# OpenEVSE_PLUS_v3.net
KiCad netlist of a schematic drawn in EAGLE
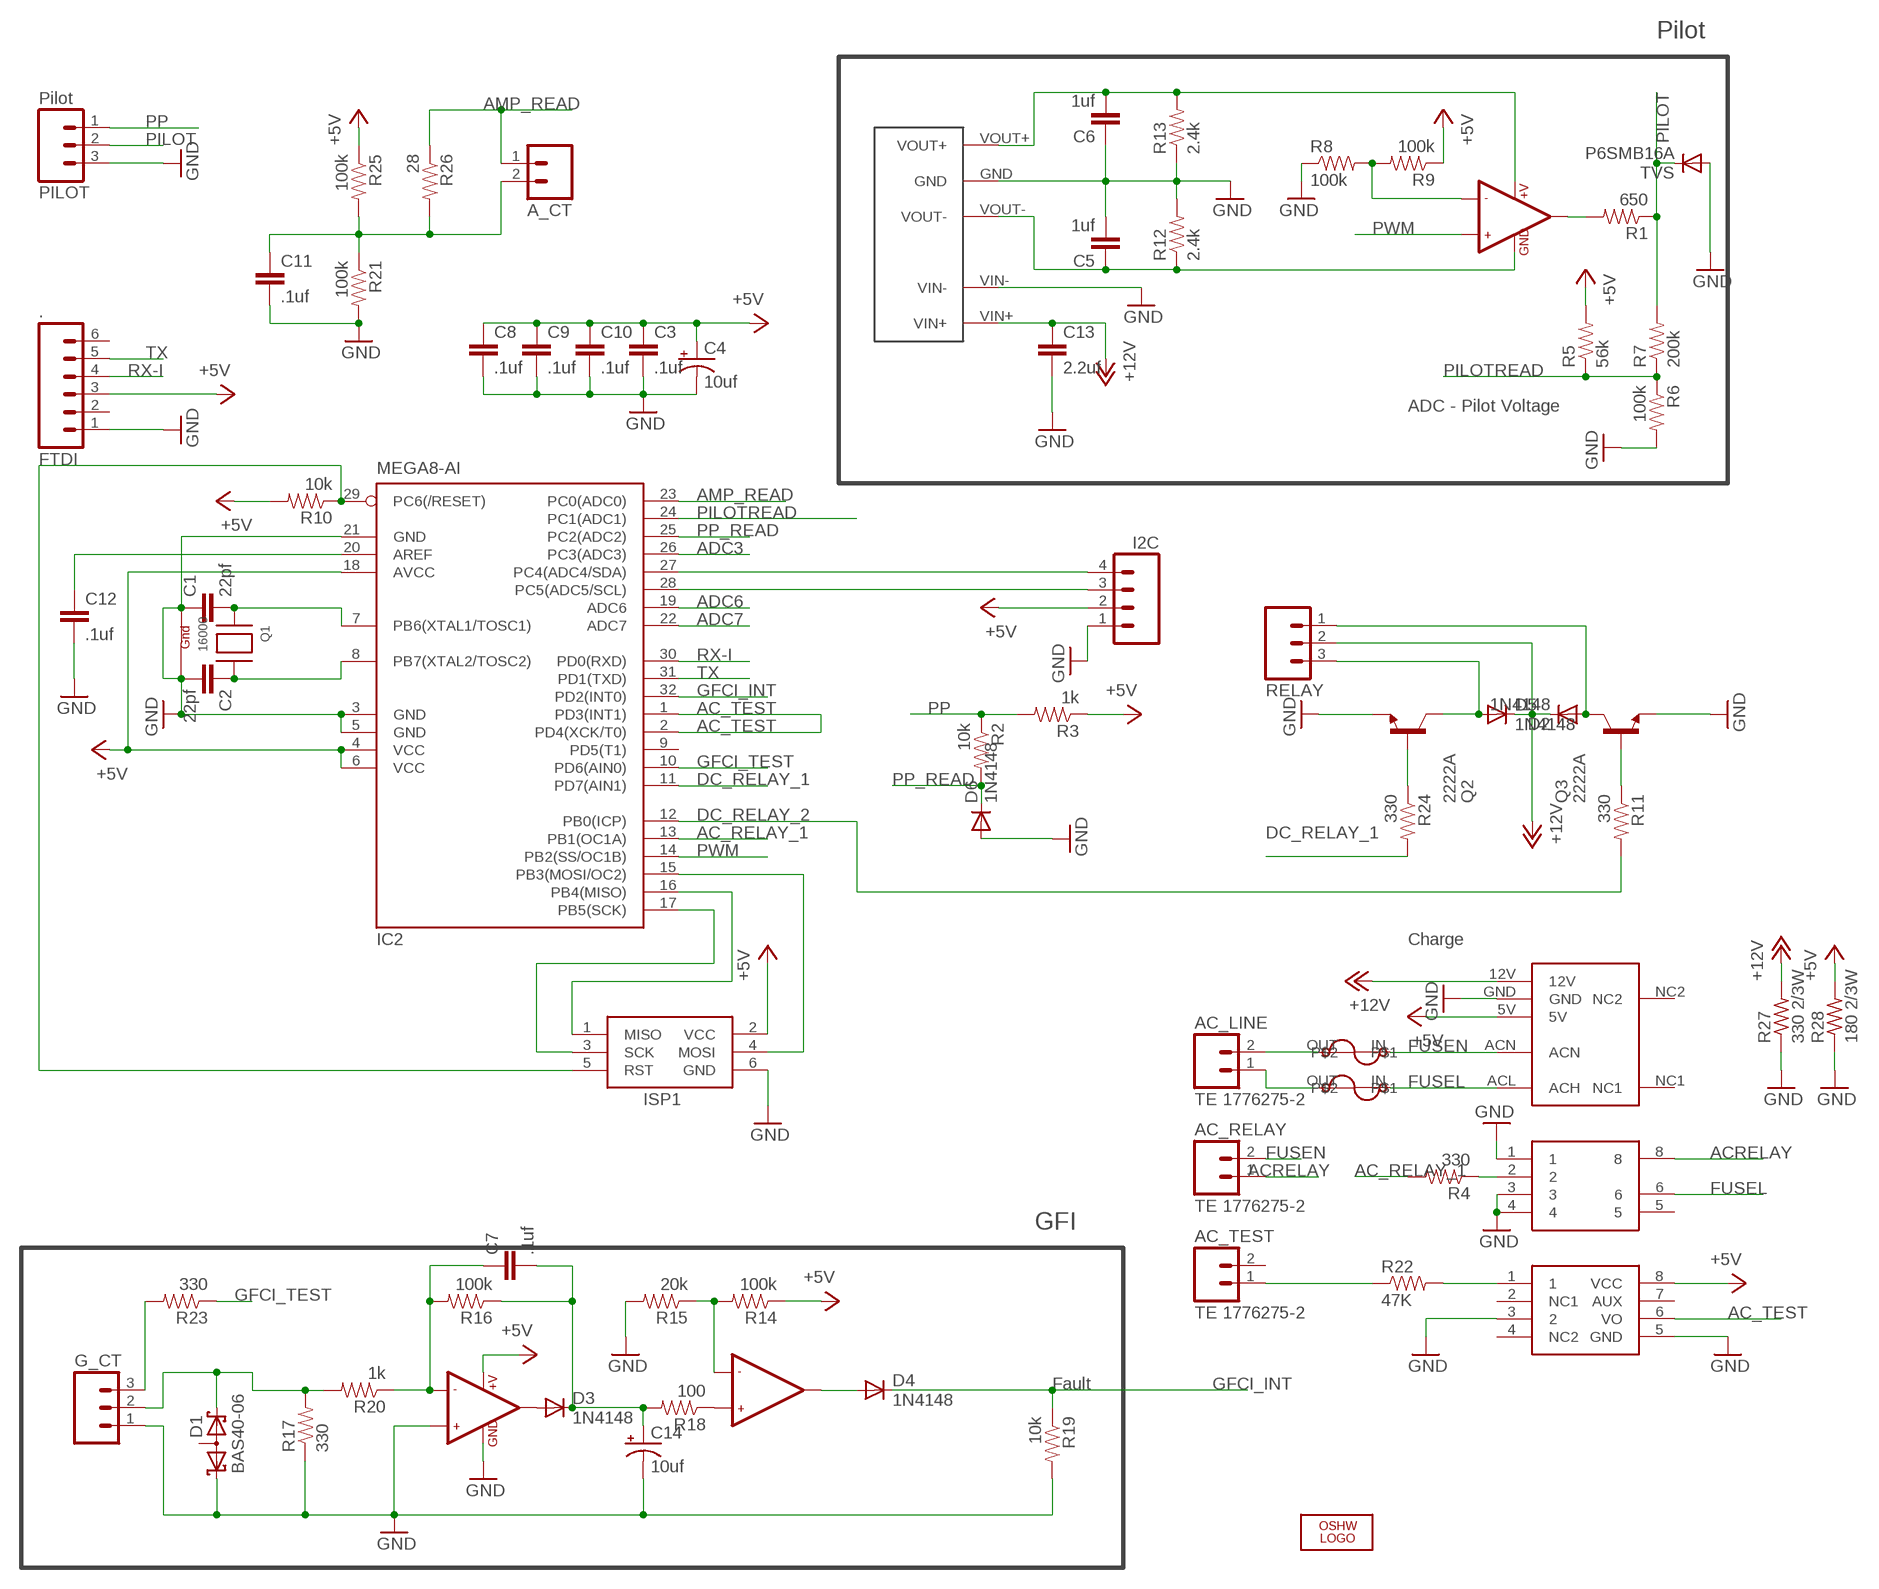
[diagram p0: schematic, sheet 1]

(export (version "E")
  (design (tool "Eeschema 10.0.6"))
  (components
    (comp (ref ".")
      (value "FTDI")
      (footprint "eagle-import:1X06_LOCK")
      (libsource (lib "eagle-import") (part "M06LOCK"))
    )
    (comp (ref "AC_LINE")
      (value "TE 1776275-2")
      (footprint "eagle-import:SCREWTERMINAL-3.5MM-2_LOCK")
      (libsource (lib "eagle-import") (part "M023.5MM_LOCK"))
    )
    (comp (ref "AC_RELAY")
      (value "TE 1776275-2")
      (footprint "eagle-import:SCREWTERMINAL-3.5MM-2_LOCK")
      (libsource (lib "eagle-import") (part "M023.5MM_LOCK"))
    )
    (comp (ref "AC_TEST")
      (value "TE 1776275-2")
      (footprint "eagle-import:SCREWTERMINAL-3.5MM-2_LOCK")
      (libsource (lib "eagle-import") (part "M023.5MM_LOCK"))
    )
    (comp (ref "A_CT")
      (value "M02PTH")
      (footprint "eagle-import:1X02")
      (libsource (lib "eagle-import") (part "M02PTH"))
    )
    (comp (ref "C1")
      (value "22pf")
      (footprint "eagle-import:0805")
      (libsource (lib "eagle-import") (part "CAP0805"))
    )
    (comp (ref "C2")
      (value "22pf")
      (footprint "eagle-import:0805")
      (libsource (lib "eagle-import") (part "CAP0805"))
    )
    (comp (ref "C3")
      (value ".1uf")
      (footprint "eagle-import:0805")
      (libsource (lib "eagle-import") (part "CAP0805"))
    )
    (comp (ref "C4")
      (value "10uf")
      (footprint "eagle-import:EIA3216")
      (libsource (lib "eagle-import") (part "CAP_POL1206"))
    )
    (comp (ref "C5")
      (value "1uf")
      (footprint "eagle-import:0805")
      (libsource (lib "eagle-import") (part "CAP0805"))
    )
    (comp (ref "C6")
      (value "1uf")
      (footprint "eagle-import:0805")
      (libsource (lib "eagle-import") (part "CAP0805"))
    )
    (comp (ref "C7")
      (value ".1uf")
      (footprint "eagle-import:0805")
      (libsource (lib "eagle-import") (part "CAP0805"))
    )
    (comp (ref "C8")
      (value ".1uf")
      (footprint "eagle-import:0805")
      (libsource (lib "eagle-import") (part "CAP0805"))
    )
    (comp (ref "C9")
      (value ".1uf")
      (footprint "eagle-import:0805")
      (libsource (lib "eagle-import") (part "CAP0805"))
    )
    (comp (ref "C10")
      (value ".1uf")
      (footprint "eagle-import:0805")
      (libsource (lib "eagle-import") (part "CAP0805"))
    )
    (comp (ref "C11")
      (value ".1uf")
      (footprint "eagle-import:0805")
      (libsource (lib "eagle-import") (part "CAP0805"))
    )
    (comp (ref "C12")
      (value ".1uf")
      (footprint "eagle-import:0805")
      (libsource (lib "eagle-import") (part "CAP0805"))
    )
    (comp (ref "C13")
      (value "2.2uf")
      (footprint "eagle-import:0805")
      (libsource (lib "eagle-import") (part "CAP0805"))
    )
    (comp (ref "C14")
      (value "10uf")
      (footprint "eagle-import:EIA3216")
      (libsource (lib "eagle-import") (part "CAP_POL1206"))
    )
    (comp (ref "D1")
      (value "BAS40-06")
      (footprint "eagle-import:SOT23")
      (libsource (lib "eagle-import") (part "BAS40-06"))
    )
    (comp (ref "D2")
      (value "1N4148")
      (footprint "eagle-import:SOD123")
      (libsource (lib "eagle-import") (part "DIODE-SOD123"))
    )
    (comp (ref "D3")
      (value "1N4148")
      (footprint "eagle-import:SOD123")
      (libsource (lib "eagle-import") (part "DIODE-SOD123"))
    )
    (comp (ref "D4")
      (value "1N4148")
      (footprint "eagle-import:SOD123")
      (libsource (lib "eagle-import") (part "DIODE-SOD123"))
    )
    (comp (ref "D5")
      (value "1N4148")
      (footprint "eagle-import:SOD123")
      (libsource (lib "eagle-import") (part "DIODE-SOD123"))
    )
    (comp (ref "D6")
      (value "1N4148")
      (footprint "eagle-import:SOD123")
      (libsource (lib "eagle-import") (part "DIODE-SOD123"))
    )
    (comp (ref "DCDC")
      (value "D107E")
      (footprint "eagle-import:DCDC_SIP")
      (libsource (lib "eagle-import") (part "DCDC_SIP"))
    )
    (comp (ref "F1")
      (value "BEL1AFUSE")
      (footprint "eagle-import:BELFUSE1A")
      (libsource (lib "eagle-import") (part "BEL1AFUSE"))
    )
    (comp (ref "F2")
      (value "BEL1AFUSE")
      (footprint "eagle-import:BELFUSE1A")
      (libsource (lib "eagle-import") (part "BEL1AFUSE"))
    )
    (comp (ref "G_CT")
      (value "M03LOCK")
      (footprint "eagle-import:1X03_LOCK")
      (libsource (lib "eagle-import") (part "M03LOCK"))
    )
    (comp (ref "I2C")
      (value "M04LOCK")
      (footprint "eagle-import:1X04_LOCK")
      (libsource (lib "eagle-import") (part "M04LOCK"))
    )
    (comp (ref "IC2")
      (value "MEGA8-AI")
      (footprint "eagle-import:TQFP32-08")
      (fields (field (name "MPN") "ATMEGA8-16AU"))
      (libsource (lib "eagle-import") (part "MEGA8-AI"))
    )
    (comp (ref "IC3")
      (value "LMV358")
      (footprint "eagle-import:SO08")
      (libsource (lib "eagle-import") (part "LMV358"))
    )
    (comp (ref "IC4")
      (value "LMV358")
      (footprint "eagle-import:SO08")
      (libsource (lib "eagle-import") (part "LMV358"))
    )
    (comp (ref "IC5")
      (value "AQH1213")
      (footprint "eagle-import:DIP7")
      (libsource (lib "eagle-import") (part "AQH1213"))
    )
    (comp (ref "IC6")
      (value "MID400")
      (footprint "eagle-import:DIP08")
      (libsource (lib "eagle-import") (part "MID400"))
    )
    (comp (ref "ISP1")
      (value "AVRISP-6")
      (footprint "eagle-import:AVRISP")
      (libsource (lib "eagle-import") (part "AVRISP-6"))
    )
    (comp (ref "LOGO1")
      (value "OSHW_LOGO_8MILX0150-NT")
      (footprint "eagle-import:OSHW_8X150_NOTEXT")
      (libsource (lib "eagle-import") (part "OSHW_LOGO_8MILX0150-NT"))
    )
    (comp (ref "PILOT")
      (value "Pilot")
      (footprint "eagle-import:SCREWTERMINAL-3.5MM-3_LOCK.007S")
      (libsource (lib "eagle-import") (part "M03SCREW_LOCK"))
    )
    (comp (ref "Q1")
      (value "16000")
      (footprint "eagle-import:NX3225")
      (libsource (lib "eagle-import") (part "XTAL-4-3225"))
    )
    (comp (ref "Q2")
      (value "2222A")
      (footprint "eagle-import:SOT23")
      (libsource (lib "eagle-import") (part "BCX70SMD"))
    )
    (comp (ref "Q3")
      (value "2222A")
      (footprint "eagle-import:SOT23")
      (libsource (lib "eagle-import") (part "BCX70SMD"))
    )
    (comp (ref "R1")
      (value "650")
      (footprint "eagle-import:0805")
      (libsource (lib "eagle-import") (part "RESISTOR0805-RES"))
    )
    (comp (ref "R2")
      (value "10k")
      (footprint "eagle-import:0805")
      (libsource (lib "eagle-import") (part "RESISTOR0805-RES"))
    )
    (comp (ref "R3")
      (value "1k")
      (footprint "eagle-import:0805")
      (libsource (lib "eagle-import") (part "RESISTOR0805-RES"))
    )
    (comp (ref "R4")
      (value "330")
      (footprint "eagle-import:0805")
      (libsource (lib "eagle-import") (part "RESISTOR0805-RES"))
    )
    (comp (ref "R5")
      (value "56k")
      (footprint "eagle-import:0805")
      (libsource (lib "eagle-import") (part "RESISTOR0805-RES"))
    )
    (comp (ref "R6")
      (value "100k")
      (footprint "eagle-import:0805")
      (libsource (lib "eagle-import") (part "RESISTOR0805-RES"))
    )
    (comp (ref "R7")
      (value "200k")
      (footprint "eagle-import:0805")
      (libsource (lib "eagle-import") (part "RESISTOR0805-RES"))
    )
    (comp (ref "R8")
      (value "100k")
      (footprint "eagle-import:0805")
      (libsource (lib "eagle-import") (part "RESISTOR0805-RES"))
    )
    (comp (ref "R9")
      (value "100k")
      (footprint "eagle-import:0805")
      (libsource (lib "eagle-import") (part "RESISTOR0805-RES"))
    )
    (comp (ref "R10")
      (value "10k")
      (footprint "eagle-import:0805")
      (libsource (lib "eagle-import") (part "RESISTOR0805-RES"))
    )
    (comp (ref "R11")
      (value "330")
      (footprint "eagle-import:0805")
      (libsource (lib "eagle-import") (part "RESISTOR0805-RES"))
    )
    (comp (ref "R12")
      (value "2.4k")
      (footprint "eagle-import:0805")
      (libsource (lib "eagle-import") (part "RESISTOR0805-RES"))
    )
    (comp (ref "R13")
      (value "2.4k")
      (footprint "eagle-import:0805")
      (libsource (lib "eagle-import") (part "RESISTOR0805-RES"))
    )
    (comp (ref "R14")
      (value "100k")
      (footprint "eagle-import:0805")
      (libsource (lib "eagle-import") (part "RESISTOR0805-RES"))
    )
    (comp (ref "R15")
      (value "20k")
      (footprint "eagle-import:0805")
      (libsource (lib "eagle-import") (part "RESISTOR0805-RES"))
    )
    (comp (ref "R16")
      (value "100k")
      (footprint "eagle-import:0805")
      (libsource (lib "eagle-import") (part "RESISTOR0805-RES"))
    )
    (comp (ref "R17")
      (value "330")
      (footprint "eagle-import:0805")
      (libsource (lib "eagle-import") (part "RESISTOR0805-RES"))
    )
    (comp (ref "R18")
      (value "100")
      (footprint "eagle-import:0805")
      (libsource (lib "eagle-import") (part "RESISTOR0805-RES"))
    )
    (comp (ref "R19")
      (value "10k")
      (footprint "eagle-import:0805")
      (libsource (lib "eagle-import") (part "RESISTOR0805-RES"))
    )
    (comp (ref "R20")
      (value "1k")
      (footprint "eagle-import:0805")
      (libsource (lib "eagle-import") (part "RESISTOR0805-RES"))
    )
    (comp (ref "R21")
      (value "100k")
      (footprint "eagle-import:0805")
      (libsource (lib "eagle-import") (part "RESISTOR0805-RES"))
    )
    (comp (ref "R22")
      (value "47K")
      (footprint "eagle-import:AXIAL-0.4")
      (libsource (lib "eagle-import") (part "RESISTORPTH-1/4W"))
    )
    (comp (ref "R23")
      (value "330")
      (footprint "eagle-import:0805")
      (libsource (lib "eagle-import") (part "RESISTOR0805-RES"))
    )
    (comp (ref "R24")
      (value "330")
      (footprint "eagle-import:0805")
      (libsource (lib "eagle-import") (part "RESISTOR0805-RES"))
    )
    (comp (ref "R25")
      (value "100k")
      (footprint "eagle-import:0805")
      (libsource (lib "eagle-import") (part "RESISTOR0805-RES"))
    )
    (comp (ref "R26")
      (value "28")
      (footprint "eagle-import:0805")
      (libsource (lib "eagle-import") (part "RESISTOR0805-RES"))
    )
    (comp (ref "R27")
      (value "330 2/3W")
      (footprint "eagle-import:R1206")
      (libsource (lib "eagle-import") (part "R-US_R1206"))
    )
    (comp (ref "R28")
      (value "180 2/3W")
      (footprint "eagle-import:R1206")
      (libsource (lib "eagle-import") (part "R-US_R1206"))
    )
    (comp (ref "RELAY")
      (value "M03SCREW_LOCK")
      (footprint "eagle-import:SCREWTERMINAL-3.5MM-3_LOCK.007S")
      (libsource (lib "eagle-import") (part "M03SCREW_LOCK"))
    )
    (comp (ref "TVS")
      (value "P6SMB16A")
      (footprint "eagle-import:SMB")
      (libsource (lib "eagle-import") (part "DIODE-SMB"))
    )
    (comp (ref "U$1")
      (value "MPM-04E-1205")
      (footprint "eagle-import:MPM-04E-1205")
      (libsource (lib "eagle-import") (part "MPM-04E-1205"))
    )
  )
  (nets
    (net (code "1") (name "+5V") (class "Default")
      (node (ref ".") (pin "3") (pinfunction "3_3") (pintype "passive"))
      (node (ref "C10") (pin "1") (pinfunction "1_1") (pintype "passive"))
      (node (ref "C3") (pin "1") (pinfunction "1_1") (pintype "passive"))
      (node (ref "C4") (pin "A") (pinfunction "+_A") (pintype "passive"))
      (node (ref "C8") (pin "1") (pinfunction "1_1") (pintype "passive"))
      (node (ref "C9") (pin "1") (pinfunction "1_1") (pintype "passive"))
      (node (ref "I2C") (pin "2") (pinfunction "2_2") (pintype "passive"))
      (node (ref "IC2") (pin "18") (pinfunction "AVCC_18") (pintype "power_in"))
      (node (ref "IC2") (pin "4") (pinfunction "VCC_4") (pintype "power_in"))
      (node (ref "IC2") (pin "6") (pinfunction "VCC_6") (pintype "power_in"))
      (node (ref "IC3") (pin "8") (pinfunction "+V_8") (pintype "power_in"))
      (node (ref "IC6") (pin "8") (pinfunction "VCC_8") (pintype "bidirectional"))
      (node (ref "ISP1") (pin "2") (pinfunction "VCC_2") (pintype "power_in"))
      (node (ref "R10") (pin "2") (pinfunction "2_2") (pintype "passive"))
      (node (ref "R14") (pin "1") (pinfunction "1_1") (pintype "passive"))
      (node (ref "R25") (pin "1") (pinfunction "1_1") (pintype "passive"))
      (node (ref "R28") (pin "2") (pinfunction "2_2") (pintype "passive"))
      (node (ref "R3") (pin "1") (pinfunction "1_1") (pintype "passive"))
      (node (ref "R5") (pin "2") (pinfunction "2_2") (pintype "passive"))
      (node (ref "R9") (pin "1") (pinfunction "1_1") (pintype "passive"))
      (node (ref "U$1") (pin "5V") (pinfunction "5V_5V") (pintype "bidirectional"))
    )
    (net (code "2") (name "+12V") (class "Default")
      (node (ref "C13") (pin "1") (pinfunction "1_1") (pintype "passive"))
      (node (ref "D2") (pin "C") (pinfunction "C_C") (pintype "passive"))
      (node (ref "D5") (pin "C") (pinfunction "C_C") (pintype "passive"))
      (node (ref "DCDC") (pin "VIN+") (pinfunction "VIN+_VIN+") (pintype "bidirectional"))
      (node (ref "R27") (pin "2") (pinfunction "2_2") (pintype "passive"))
      (node (ref "RELAY") (pin "2") (pinfunction "2_2") (pintype "passive"))
      (node (ref "U$1") (pin "12V") (pinfunction "12V_12V") (pintype "bidirectional"))
    )
    (net (code "3") (name "/ACRELAY") (class "Default")
      (node (ref "AC_RELAY") (pin "1") (pinfunction "1_1") (pintype "passive"))
      (node (ref "IC5") (pin "8") (pinfunction "8_8") (pintype "bidirectional"))
    )
    (net (code "4") (name "/AC_RELAY_1") (class "Default")
      (node (ref "IC2") (pin "13") (pinfunction "PB1(OC1A)_13") (pintype "bidirectional"))
      (node (ref "R4") (pin "2") (pinfunction "2_2") (pintype "passive"))
    )
    (net (code "5") (name "/AC_TEST") (class "Default")
      (node (ref "IC2") (pin "1") (pinfunction "PD3(INT1)_1") (pintype "bidirectional"))
      (node (ref "IC2") (pin "2") (pinfunction "PD4(XCK/T0)_2") (pintype "bidirectional"))
      (node (ref "IC6") (pin "6") (pinfunction "VO_6") (pintype "bidirectional"))
    )
    (net (code "6") (name "/ADC3") (class "Default")
      (node (ref "IC2") (pin "26") (pinfunction "PC3(ADC3)_26") (pintype "bidirectional"))
    )
    (net (code "7") (name "/ADC6") (class "Default")
      (node (ref "IC2") (pin "19") (pinfunction "ADC6_19") (pintype "bidirectional"))
    )
    (net (code "8") (name "/ADC7") (class "Default")
      (node (ref "IC2") (pin "22") (pinfunction "ADC7_22") (pintype "bidirectional"))
    )
    (net (code "9") (name "/AMP_READ") (class "Default")
      (node (ref "A_CT") (pin "1") (pinfunction "1_1") (pintype "passive"))
      (node (ref "IC2") (pin "23") (pinfunction "PC0(ADC0)_23") (pintype "bidirectional"))
      (node (ref "R26") (pin "1") (pinfunction "1_1") (pintype "passive"))
    )
    (net (code "10") (name "/DC_RELAY_1") (class "Default")
      (node (ref "IC2") (pin "11") (pinfunction "PD7(AIN1)_11") (pintype "bidirectional"))
      (node (ref "R24") (pin "2") (pinfunction "2_2") (pintype "passive"))
    )
    (net (code "11") (name "/DC_RELAY_2") (class "Default")
      (node (ref "IC2") (pin "12") (pinfunction "PB0(ICP)_12") (pintype "bidirectional"))
      (node (ref "R11") (pin "2") (pinfunction "2_2") (pintype "passive"))
    )
    (net (code "12") (name "/FUSEL") (class "Default")
      (node (ref "F2") (pin "IN") (pinfunction "P$2_IN") (pintype "bidirectional"))
      (node (ref "IC5") (pin "6") (pinfunction "6_6") (pintype "bidirectional"))
      (node (ref "U$1") (pin "ACL") (pinfunction "ACH_ACL") (pintype "bidirectional"))
    )
    (net (code "13") (name "/FUSEN") (class "Default")
      (node (ref "AC_RELAY") (pin "2") (pinfunction "2_2") (pintype "passive"))
      (node (ref "F1") (pin "IN") (pinfunction "P$2_IN") (pintype "bidirectional"))
      (node (ref "U$1") (pin "ACN") (pinfunction "ACN_ACN") (pintype "bidirectional"))
    )
    (net (code "14") (name "/GFCI_INT") (class "Default")
      (node (ref "D4") (pin "C") (pinfunction "C_C") (pintype "passive"))
      (node (ref "IC2") (pin "32") (pinfunction "PD2(INT0)_32") (pintype "bidirectional"))
      (node (ref "R19") (pin "1") (pinfunction "1_1") (pintype "passive"))
    )
    (net (code "15") (name "/GFCI_TEST") (class "Default")
      (node (ref "IC2") (pin "10") (pinfunction "PD6(AIN0)_10") (pintype "bidirectional"))
      (node (ref "R23") (pin "1") (pinfunction "1_1") (pintype "passive"))
    )
    (net (code "16") (name "/PILOT") (class "Default")
      (node (ref "PILOT") (pin "2") (pinfunction "2_2") (pintype "passive"))
      (node (ref "R1") (pin "1") (pinfunction "1_1") (pintype "passive"))
      (node (ref "R7") (pin "2") (pinfunction "2_2") (pintype "passive"))
      (node (ref "TVS") (pin "C") (pinfunction "C_C") (pintype "passive"))
    )
    (net (code "17") (name "/PILOTREAD") (class "Default")
      (node (ref "IC2") (pin "24") (pinfunction "PC1(ADC1)_24") (pintype "bidirectional"))
      (node (ref "R5") (pin "1") (pinfunction "1_1") (pintype "passive"))
      (node (ref "R6") (pin "1") (pinfunction "1_1") (pintype "passive"))
      (node (ref "R7") (pin "1") (pinfunction "1_1") (pintype "passive"))
    )
    (net (code "18") (name "/PP") (class "Default")
      (node (ref "PILOT") (pin "1") (pinfunction "1_1") (pintype "passive"))
      (node (ref "R2") (pin "1") (pinfunction "1_1") (pintype "passive"))
      (node (ref "R3") (pin "2") (pinfunction "2_2") (pintype "passive"))
    )
    (net (code "19") (name "/PP_READ") (class "Default")
      (node (ref "D6") (pin "C") (pinfunction "C_C") (pintype "passive"))
      (node (ref "IC2") (pin "25") (pinfunction "PC2(ADC2)_25") (pintype "bidirectional"))
      (node (ref "R2") (pin "2") (pinfunction "2_2") (pintype "passive"))
    )
    (net (code "20") (name "/PWM") (class "Default")
      (node (ref "IC2") (pin "14") (pinfunction "PB2(SS/OC1B)_14") (pintype "bidirectional"))
      (node (ref "IC4") (pin "3") (pinfunction "+IN1_3") (pintype "input"))
    )
    (net (code "21") (name "/RX-I") (class "Default")
      (node (ref ".") (pin "4") (pinfunction "4_4") (pintype "passive"))
      (node (ref "IC2") (pin "30") (pinfunction "PD0(RXD)_30") (pintype "bidirectional"))
    )
    (net (code "22") (name "/TX") (class "Default")
      (node (ref ".") (pin "5") (pinfunction "5_5") (pintype "passive"))
      (node (ref "IC2") (pin "31") (pinfunction "PD1(TXD)_31") (pintype "bidirectional"))
    )
    (net (code "23") (name "GND") (class "Default")
      (node (ref ".") (pin "1") (pinfunction "1_1") (pintype "passive"))
      (node (ref "C1") (pin "1") (pinfunction "1_1") (pintype "passive"))
      (node (ref "C10") (pin "2") (pinfunction "2_2") (pintype "passive"))
      (node (ref "C11") (pin "2") (pinfunction "2_2") (pintype "passive"))
      (node (ref "C12") (pin "2") (pinfunction "2_2") (pintype "passive"))
      (node (ref "C13") (pin "2") (pinfunction "2_2") (pintype "passive"))
      (node (ref "C14") (pin "C") (pinfunction "-_C") (pintype "passive"))
      (node (ref "C2") (pin "2") (pinfunction "2_2") (pintype "passive"))
      (node (ref "C3") (pin "2") (pinfunction "2_2") (pintype "passive"))
      (node (ref "C4") (pin "C") (pinfunction "-_C") (pintype "passive"))
      (node (ref "C5") (pin "2") (pinfunction "2_2") (pintype "passive"))
      (node (ref "C6") (pin "1") (pinfunction "1_1") (pintype "passive"))
      (node (ref "C8") (pin "2") (pinfunction "2_2") (pintype "passive"))
      (node (ref "C9") (pin "2") (pinfunction "2_2") (pintype "passive"))
      (node (ref "D1") (pin "1") (pinfunction "K1_1") (pintype "passive"))
      (node (ref "D6") (pin "A") (pinfunction "A_A") (pintype "passive"))
      (node (ref "DCDC") (pin "GND") (pinfunction "GND_GND") (pintype "bidirectional"))
      (node (ref "DCDC") (pin "VIN-") (pinfunction "VIN-_VIN-") (pintype "bidirectional"))
      (node (ref "G_CT") (pin "1") (pinfunction "1_1") (pintype "passive"))
      (node (ref "I2C") (pin "1") (pinfunction "1_1") (pintype "passive"))
      (node (ref "IC2") (pin "21") (pinfunction "GND_21") (pintype "power_in"))
      (node (ref "IC2") (pin "3") (pinfunction "GND_3") (pintype "power_in"))
      (node (ref "IC2") (pin "5") (pinfunction "GND_5") (pintype "power_in"))
      (node (ref "IC3") (pin "3") (pinfunction "+IN1_3") (pintype "input"))
      (node (ref "IC3") (pin "4") (pinfunction "GND_4") (pintype "power_in"))
      (node (ref "IC5") (pin "1") (pinfunction "1_1") (pintype "bidirectional"))
      (node (ref "IC5") (pin "3") (pinfunction "3_3") (pintype "bidirectional"))
      (node (ref "IC5") (pin "4") (pinfunction "4_4") (pintype "bidirectional"))
      (node (ref "IC6") (pin "3") (pinfunction "2_3") (pintype "bidirectional"))
      (node (ref "IC6") (pin "5") (pinfunction "GND_5") (pintype "bidirectional"))
      (node (ref "ISP1") (pin "6") (pinfunction "GND_6") (pintype "power_in"))
      (node (ref "PILOT") (pin "3") (pinfunction "3_3") (pintype "passive"))
      (node (ref "Q1") (pin "1") (pinfunction "G1_1") (pintype "power_in"))
      (node (ref "Q1") (pin "3") (pinfunction "G2_3") (pintype "power_in"))
      (node (ref "Q2") (pin "2") (pinfunction "E_2") (pintype "passive"))
      (node (ref "Q3") (pin "2") (pinfunction "E_2") (pintype "passive"))
      (node (ref "R12") (pin "2") (pinfunction "2_2") (pintype "passive"))
      (node (ref "R13") (pin "1") (pinfunction "1_1") (pintype "passive"))
      (node (ref "R15") (pin "2") (pinfunction "2_2") (pintype "passive"))
      (node (ref "R17") (pin "1") (pinfunction "1_1") (pintype "passive"))
      (node (ref "R19") (pin "2") (pinfunction "2_2") (pintype "passive"))
      (node (ref "R21") (pin "2") (pinfunction "2_2") (pintype "passive"))
      (node (ref "R27") (pin "1") (pinfunction "1_1") (pintype "passive"))
      (node (ref "R28") (pin "1") (pinfunction "1_1") (pintype "passive"))
      (node (ref "R6") (pin "2") (pinfunction "2_2") (pintype "passive"))
      (node (ref "R8") (pin "1") (pinfunction "1_1") (pintype "passive"))
      (node (ref "TVS") (pin "A") (pinfunction "A_A") (pintype "passive"))
      (node (ref "U$1") (pin "GND") (pinfunction "GND_GND") (pintype "bidirectional"))
    )
    (net (code "24") (name "Net-(A_CT-Pad2)") (class "Default")
      (node (ref "A_CT") (pin "2") (pinfunction "2_2") (pintype "passive"))
      (node (ref "C11") (pin "1") (pinfunction "1_1") (pintype "passive"))
      (node (ref "R21") (pin "1") (pinfunction "1_1") (pintype "passive"))
      (node (ref "R25") (pin "2") (pinfunction "2_2") (pintype "passive"))
      (node (ref "R26") (pin "2") (pinfunction "2_2") (pintype "passive"))
    )
    (net (code "25") (name "Net-(C14-+)") (class "Default")
      (node (ref "C14") (pin "A") (pinfunction "+_A") (pintype "passive"))
      (node (ref "C7") (pin "2") (pinfunction "2_2") (pintype "passive"))
      (node (ref "D3") (pin "C") (pinfunction "C_C") (pintype "passive"))
      (node (ref "R16") (pin "1") (pinfunction "1_1") (pintype "passive"))
      (node (ref "R18") (pin "2") (pinfunction "2_2") (pintype "passive"))
    )
    (net (code "26") (name "Net-(D1-K2)") (class "Default")
      (node (ref "D1") (pin "2") (pinfunction "K2_2") (pintype "passive"))
      (node (ref "G_CT") (pin "2") (pinfunction "2_2") (pintype "passive"))
      (node (ref "R17") (pin "2") (pinfunction "2_2") (pintype "passive"))
      (node (ref "R20") (pin "2") (pinfunction "2_2") (pintype "passive"))
    )
    (net (code "27") (name "Net-(F1-P$1)") (class "Default")
      (node (ref "AC_LINE") (pin "2") (pinfunction "2_2") (pintype "passive"))
      (node (ref "F1") (pin "OUT") (pinfunction "P$1_OUT") (pintype "bidirectional"))
    )
    (net (code "28") (name "Net-(F2-P$1)") (class "Default")
      (node (ref "AC_LINE") (pin "1") (pinfunction "1_1") (pintype "passive"))
      (node (ref "F2") (pin "OUT") (pinfunction "P$1_OUT") (pintype "bidirectional"))
    )
    (net (code "29") (name "Net-(G_CT-Pad3)") (class "Default")
      (node (ref "G_CT") (pin "3") (pinfunction "3_3") (pintype "passive"))
      (node (ref "R23") (pin "2") (pinfunction "2_2") (pintype "passive"))
    )
    (net (code "30") (name "Net-(IC2-AREF)") (class "Default")
      (node (ref "C12") (pin "1") (pinfunction "1_1") (pintype "passive"))
      (node (ref "IC2") (pin "20") (pinfunction "AREF_20") (pintype "passive"))
    )
    (net (code "31") (name "Net-(IC2-PB3(MOSI{slash}OC2))") (class "Default")
      (node (ref "IC2") (pin "15") (pinfunction "PB3(MOSI/OC2)_15") (pintype "bidirectional"))
      (node (ref "ISP1") (pin "4") (pinfunction "MOSI_4") (pintype "output"))
    )
    (net (code "32") (name "Net-(IC2-PB4(MISO))") (class "Default")
      (node (ref "IC2") (pin "16") (pinfunction "PB4(MISO)_16") (pintype "bidirectional"))
      (node (ref "ISP1") (pin "1") (pinfunction "MISO_1") (pintype "input"))
    )
    (net (code "33") (name "Net-(IC2-PB5(SCK))") (class "Default")
      (node (ref "IC2") (pin "17") (pinfunction "PB5(SCK)_17") (pintype "bidirectional"))
      (node (ref "ISP1") (pin "3") (pinfunction "SCK_3") (pintype "output"))
    )
    (net (code "34") (name "Net-(IC2-PB6(XTAL1{slash}TOSC1))") (class "Default")
      (node (ref "C1") (pin "2") (pinfunction "2_2") (pintype "passive"))
      (node (ref "IC2") (pin "7") (pinfunction "PB6(XTAL1/TOSC1)_7") (pintype "bidirectional"))
      (node (ref "Q1") (pin "2") (pinfunction "X1_2") (pintype "bidirectional"))
    )
    (net (code "35") (name "Net-(IC2-PB7(XTAL2{slash}TOSC2))") (class "Default")
      (node (ref "C2") (pin "1") (pinfunction "1_1") (pintype "passive"))
      (node (ref "IC2") (pin "8") (pinfunction "PB7(XTAL2/TOSC2)_8") (pintype "bidirectional"))
      (node (ref "Q1") (pin "4") (pinfunction "X2_4") (pintype "bidirectional"))
    )
    (net (code "36") (name "Net-(IC2-PC4(ADC4{slash}SDA))") (class "Default")
      (node (ref "I2C") (pin "4") (pinfunction "4_4") (pintype "passive"))
      (node (ref "IC2") (pin "27") (pinfunction "PC4(ADC4/SDA)_27") (pintype "bidirectional"))
    )
    (net (code "37") (name "Net-(IC2-PC5(ADC5{slash}SCL))") (class "Default")
      (node (ref "I2C") (pin "3") (pinfunction "3_3") (pintype "passive"))
      (node (ref "IC2") (pin "28") (pinfunction "PC5(ADC5/SCL)_28") (pintype "bidirectional"))
    )
    (net (code "38") (name "Net-(IC2-PC6({slash}RESET))") (class "Default")
      (node (ref "IC2") (pin "29") (pinfunction "PC6(/RESET)_29") (pintype "bidirectional"))
      (node (ref "ISP1") (pin "5") (pinfunction "RST_5") (pintype "output"))
      (node (ref "R10") (pin "1") (pinfunction "1_1") (pintype "passive"))
    )
    (net (code "39") (name "Net-(IC3A--IN1)") (class "Default")
      (node (ref "C7") (pin "1") (pinfunction "1_1") (pintype "passive"))
      (node (ref "IC3") (pin "2") (pinfunction "-IN1_2") (pintype "input"))
      (node (ref "R16") (pin "2") (pinfunction "2_2") (pintype "passive"))
      (node (ref "R20") (pin "1") (pinfunction "1_1") (pintype "passive"))
    )
    (net (code "40") (name "Net-(IC3A-OUT1)") (class "Default")
      (node (ref "D3") (pin "A") (pinfunction "A_A") (pintype "passive"))
      (node (ref "IC3") (pin "1") (pinfunction "OUT1_1") (pintype "output"))
    )
    (net (code "41") (name "Net-(IC3B-+IN2)") (class "Default")
      (node (ref "IC3") (pin "5") (pinfunction "+IN2_5") (pintype "input"))
      (node (ref "R18") (pin "1") (pinfunction "1_1") (pintype "passive"))
    )
    (net (code "42") (name "Net-(IC3B--IN2)") (class "Default")
      (node (ref "IC3") (pin "6") (pinfunction "-IN2_6") (pintype "input"))
      (node (ref "R14") (pin "2") (pinfunction "2_2") (pintype "passive"))
      (node (ref "R15") (pin "1") (pinfunction "1_1") (pintype "passive"))
    )
    (net (code "43") (name "Net-(IC3B-OUT2)") (class "Default")
      (node (ref "D4") (pin "A") (pinfunction "A_A") (pintype "passive"))
      (node (ref "IC3") (pin "7") (pinfunction "OUT2_7") (pintype "output"))
    )
    (net (code "44") (name "Net-(IC4A-+V)") (class "Default")
      (node (ref "C6") (pin "2") (pinfunction "2_2") (pintype "passive"))
      (node (ref "DCDC") (pin "VOUT+") (pinfunction "VOUT+_VOUT+") (pintype "bidirectional"))
      (node (ref "IC4") (pin "8") (pinfunction "+V_8") (pintype "power_in"))
      (node (ref "R13") (pin "2") (pinfunction "2_2") (pintype "passive"))
    )
    (net (code "45") (name "Net-(IC4A--IN1)") (class "Default")
      (node (ref "IC4") (pin "2") (pinfunction "-IN1_2") (pintype "input"))
      (node (ref "R8") (pin "2") (pinfunction "2_2") (pintype "passive"))
      (node (ref "R9") (pin "2") (pinfunction "2_2") (pintype "passive"))
    )
    (net (code "46") (name "Net-(IC4A-GND)") (class "Default")
      (node (ref "C5") (pin "1") (pinfunction "1_1") (pintype "passive"))
      (node (ref "DCDC") (pin "VOUT-") (pinfunction "VOUT-_VOUT-") (pintype "bidirectional"))
      (node (ref "IC4") (pin "4") (pinfunction "GND_4") (pintype "power_in"))
      (node (ref "R12") (pin "1") (pinfunction "1_1") (pintype "passive"))
    )
    (net (code "47") (name "Net-(IC4A-OUT1)") (class "Default")
      (node (ref "IC4") (pin "1") (pinfunction "OUT1_1") (pintype "output"))
      (node (ref "R1") (pin "2") (pinfunction "2_2") (pintype "passive"))
    )
    (net (code "48") (name "Net-(IC5-Pad2)") (class "Default")
      (node (ref "IC5") (pin "2") (pinfunction "2_2") (pintype "bidirectional"))
      (node (ref "R4") (pin "1") (pinfunction "1_1") (pintype "passive"))
    )
    (net (code "49") (name "Net-(Q2-B)") (class "Default")
      (node (ref "Q2") (pin "1") (pinfunction "B_1") (pintype "passive"))
      (node (ref "R24") (pin "1") (pinfunction "1_1") (pintype "passive"))
    )
    (net (code "50") (name "Net-(Q2-C)") (class "Default")
      (node (ref "D5") (pin "A") (pinfunction "A_A") (pintype "passive"))
      (node (ref "Q2") (pin "3") (pinfunction "C_3") (pintype "passive"))
      (node (ref "RELAY") (pin "3") (pinfunction "3_3") (pintype "passive"))
    )
    (net (code "51") (name "Net-(Q3-B)") (class "Default")
      (node (ref "Q3") (pin "1") (pinfunction "B_1") (pintype "passive"))
      (node (ref "R11") (pin "1") (pinfunction "1_1") (pintype "passive"))
    )
    (net (code "52") (name "Net-(Q3-C)") (class "Default")
      (node (ref "D2") (pin "A") (pinfunction "A_A") (pintype "passive"))
      (node (ref "Q3") (pin "3") (pinfunction "C_3") (pintype "passive"))
      (node (ref "RELAY") (pin "1") (pinfunction "1_1") (pintype "passive"))
    )
    (net (code "53") (name "Net-(R22-1)") (class "Default")
      (node (ref "AC_TEST") (pin "1") (pinfunction "1_1") (pintype "passive"))
      (node (ref "R22") (pin "P$1") (pinfunction "1_P$1") (pintype "passive"))
    )
    (net (code "54") (name "Net-(R22-2)") (class "Default")
      (node (ref "IC6") (pin "1") (pinfunction "1_1") (pintype "bidirectional"))
      (node (ref "R22") (pin "P$2") (pinfunction "2_P$2") (pintype "passive"))
    )
    (net (code "55") (name "unconnected-(.-Pad2)") (class "Default")
      (node (ref ".") (pin "2") (pinfunction "2_2") (pintype "passive"))
    )
    (net (code "56") (name "unconnected-(.-Pad6)") (class "Default")
      (node (ref ".") (pin "6") (pinfunction "6_6") (pintype "passive"))
    )
    (net (code "57") (name "unconnected-(AC_TEST-Pad2)") (class "Default")
      (node (ref "AC_TEST") (pin "2") (pinfunction "2_2") (pintype "passive"))
    )
    (net (code "58") (name "unconnected-(D1-AA-Pad3)") (class "Default")
      (node (ref "D1") (pin "3") (pinfunction "AA_3") (pintype "passive"))
    )
    (net (code "59") (name "unconnected-(IC2-PD5(T1)-Pad9)") (class "Default")
      (node (ref "IC2") (pin "9") (pinfunction "PD5(T1)_9") (pintype "bidirectional"))
    )
    (net (code "60") (name "unconnected-(IC5-Pad5)") (class "Default")
      (node (ref "IC5") (pin "5") (pinfunction "5_5") (pintype "bidirectional"))
    )
    (net (code "61") (name "unconnected-(IC6-AUX-Pad7)") (class "Default")
      (node (ref "IC6") (pin "7") (pinfunction "AUX_7") (pintype "bidirectional"))
    )
    (net (code "62") (name "unconnected-(IC6-NC1-Pad2)") (class "Default")
      (node (ref "IC6") (pin "2") (pinfunction "NC1_2") (pintype "bidirectional"))
    )
    (net (code "63") (name "unconnected-(IC6-NC2-Pad4)") (class "Default")
      (node (ref "IC6") (pin "4") (pinfunction "NC2_4") (pintype "bidirectional"))
    )
    (net (code "64") (name "unconnected-(U$1-PadNC1)") (class "Default")
      (node (ref "U$1") (pin "NC1") (pinfunction "NC1_NC1") (pintype "bidirectional"))
    )
    (net (code "65") (name "unconnected-(U$1-PadNC2)") (class "Default")
      (node (ref "U$1") (pin "NC2") (pinfunction "NC2_NC2") (pintype "bidirectional"))
    )
  )
)
